# Ascend_SolePCB.net
KiCad netlist of a schematic drawn in EasyEDA Pro
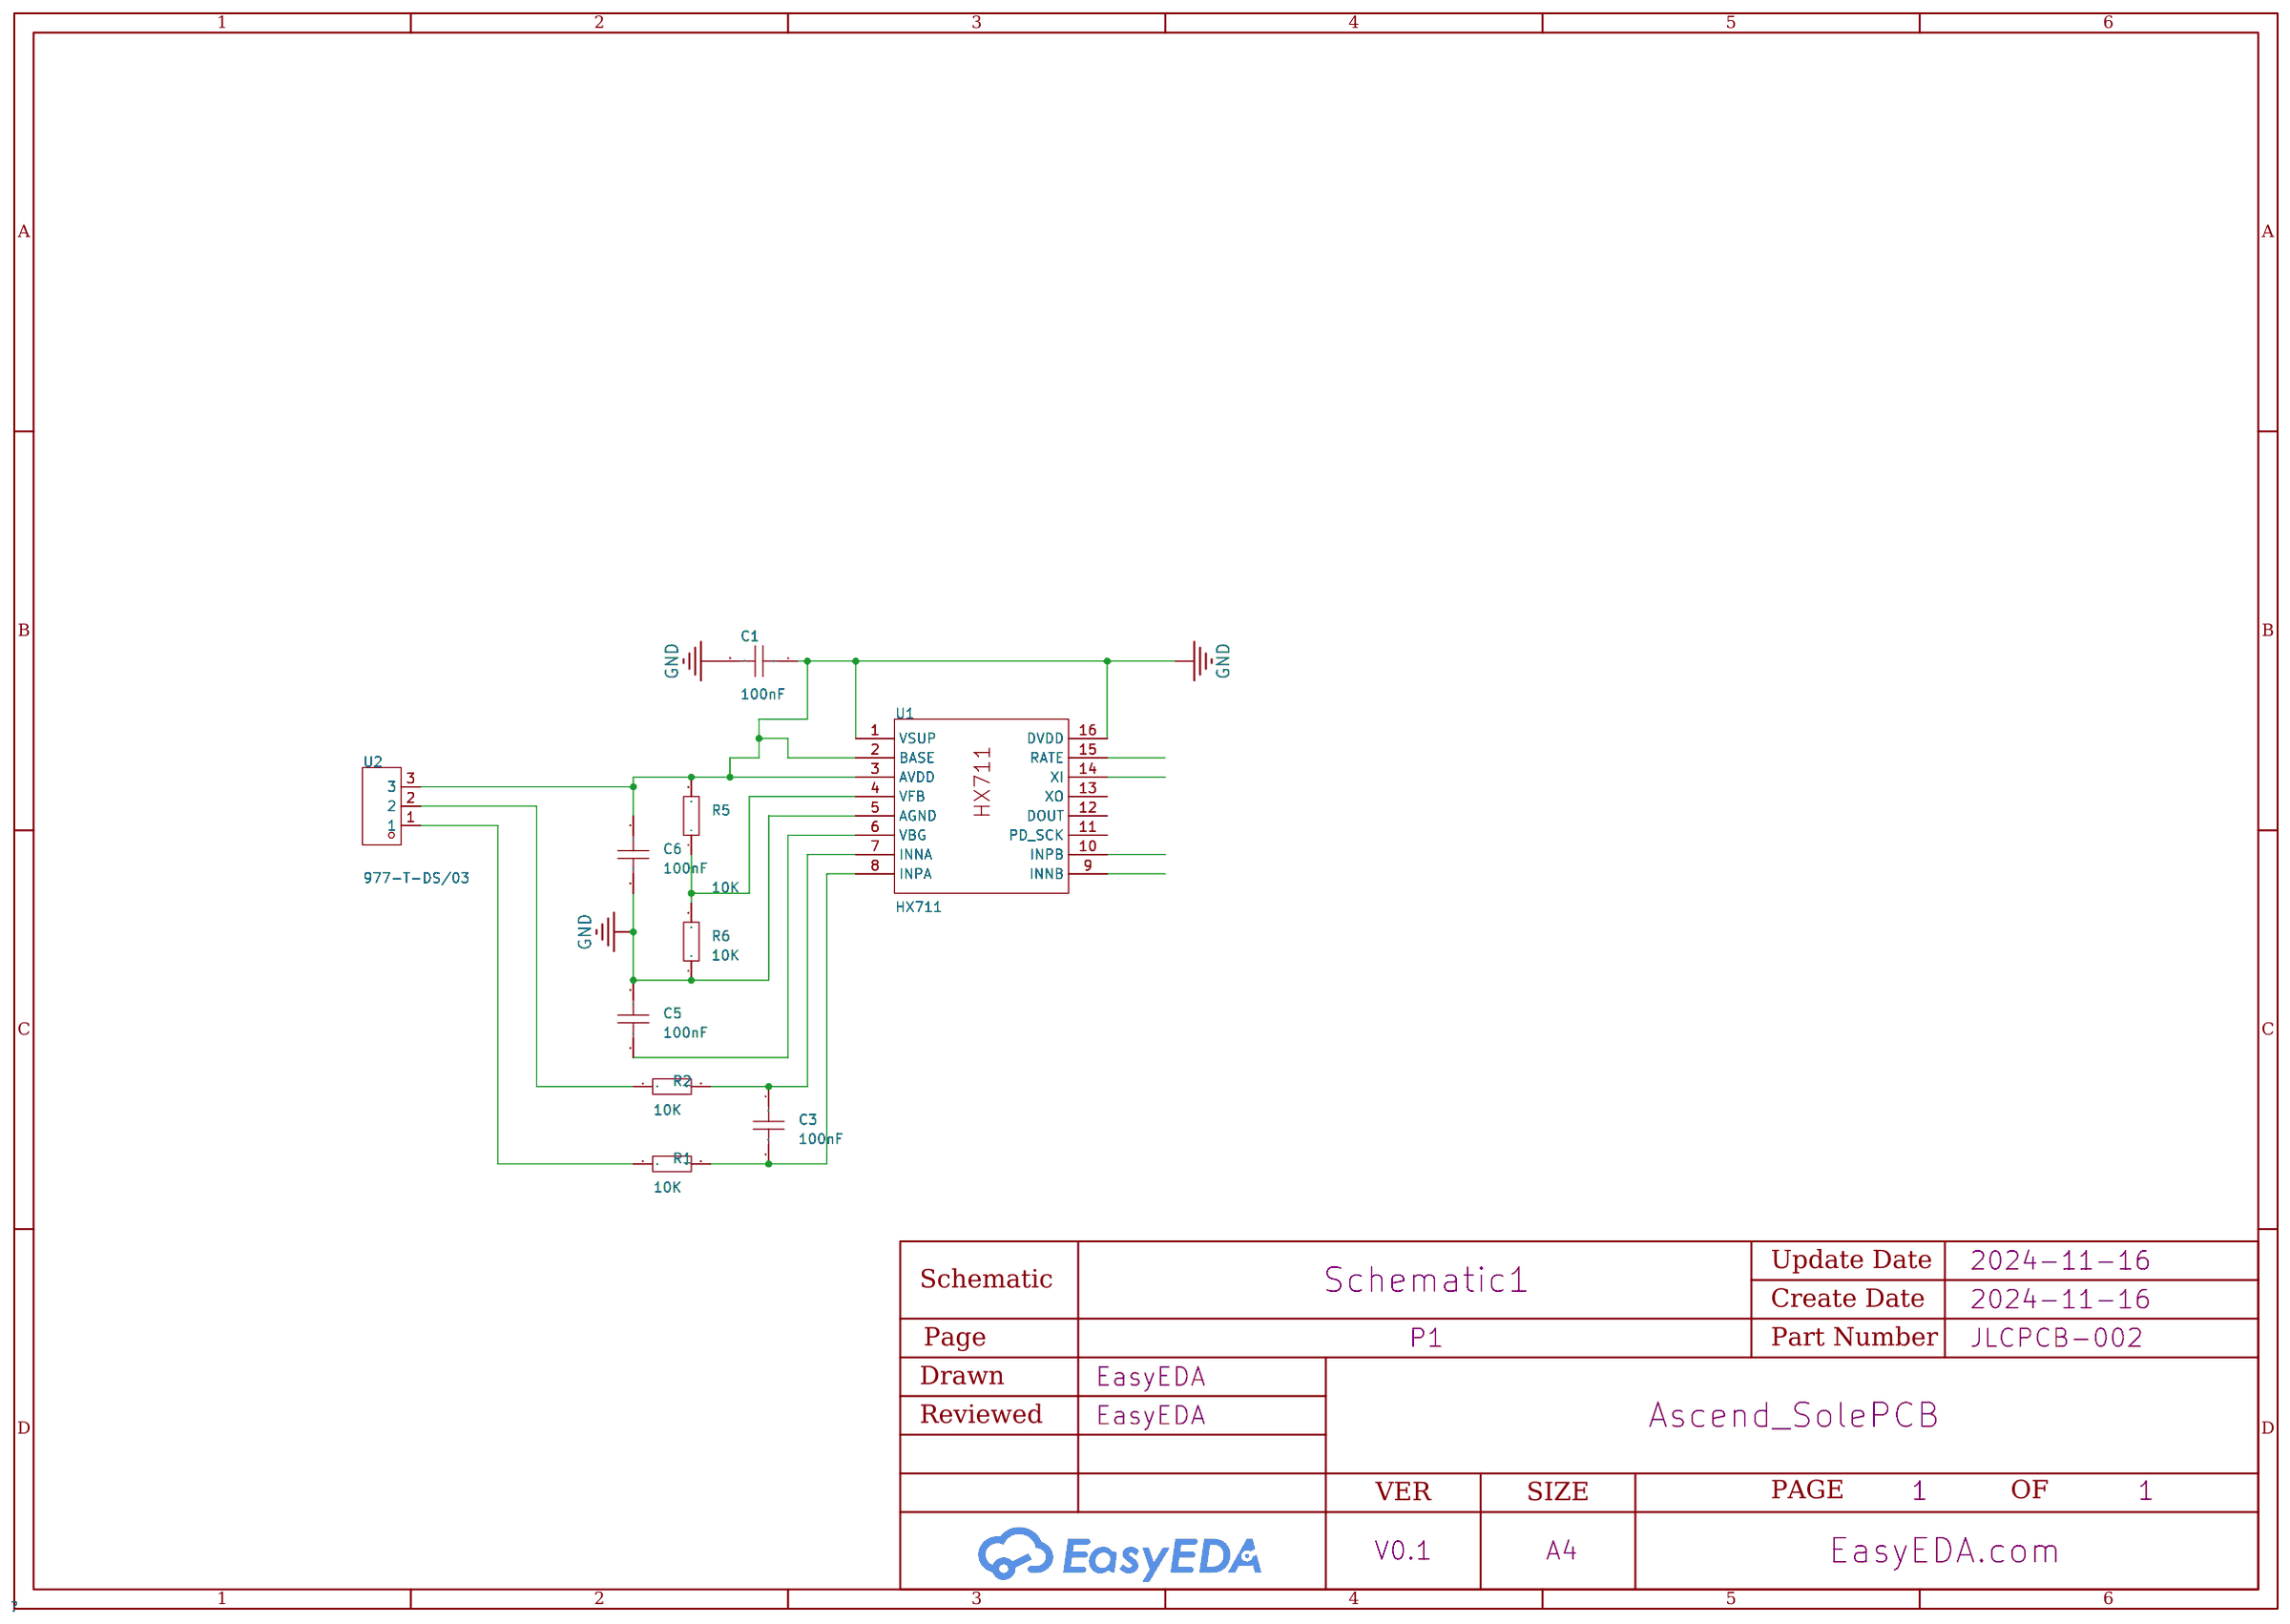
[diagram p0: schematic sheet]

(export (version "E")
  (design (tool "Eeschema 10.0.6"))
  (components
    (comp (ref "C1")
      (value "100nF")
      (footprint "easyedapro:C0201")
      (libsource (lib "easyedapro") (part "CAP"))
    )
    (comp (ref "C3")
      (value "100nF")
      (footprint "easyedapro:C0201")
      (libsource (lib "easyedapro") (part "CAP"))
    )
    (comp (ref "C5")
      (value "100nF")
      (footprint "easyedapro:C0201")
      (libsource (lib "easyedapro") (part "CAP"))
    )
    (comp (ref "C6")
      (value "100nF")
      (footprint "easyedapro:C0201")
      (libsource (lib "easyedapro") (part "CAP"))
    )
    (comp (ref "R1") (value "10K") (footprint "easyedapro:R0603") (libsource (lib "easyedapro") (part "Res")))
    (comp (ref "R2") (value "10K") (footprint "easyedapro:R0603") (libsource (lib "easyedapro") (part "Res")))
    (comp (ref "R5") (value "10K") (footprint "easyedapro:R0603") (libsource (lib "easyedapro") (part "Res")))
    (comp (ref "R6") (value "10K") (footprint "easyedapro:R0603") (libsource (lib "easyedapro") (part "Res")))
    (comp (ref "U1")
      (value "HX711")
      (footprint "easyedapro:SOP-16_L10.0-W3.9-P1.27-LS6.0-BL")
      (fields (field (name "Manufacturer") "AVIA(海芯科技)"))
      (libsource (lib "easyedapro") (part "HX711"))
    )
    (comp (ref "U2")
      (value "977-T-DS/03")
      (footprint "easyedapro:CONN-TH_3P-P7.50_977-T-DS-03")
      (fields (field (name "Manufacturer") "WECO(威克德诺)"))
      (libsource (lib "easyedapro") (part "977-T-DS/03"))
    )
  )
  (nets
    (net (code "1") (name "GND") (class "Default")
      (node (ref "C1") (pin "1") (pinfunction "1_1") (pintype "input"))
      (node (ref "C1") (pin "2") (pinfunction "2_2") (pintype "input"))
      (node (ref "C5") (pin "1") (pinfunction "1_1") (pintype "input"))
      (node (ref "C6") (pin "1") (pinfunction "1_1") (pintype "input"))
      (node (ref "C6") (pin "2") (pinfunction "2_2") (pintype "input"))
      (node (ref "R5") (pin "2") (pinfunction "2_2") (pintype "input"))
      (node (ref "R6") (pin "1") (pinfunction "1_1") (pintype "input"))
      (node (ref "U1") (pin "1") (pinfunction "VSUP_1") (pintype "unspecified"))
      (node (ref "U1") (pin "16") (pinfunction "DVDD_16") (pintype "unspecified"))
      (node (ref "U1") (pin "2") (pinfunction "BASE_2") (pintype "unspecified"))
      (node (ref "U1") (pin "3") (pinfunction "AVDD_3") (pintype "unspecified"))
      (node (ref "U1") (pin "5") (pinfunction "AGND_5") (pintype "unspecified"))
      (node (ref "U2") (pin "3") (pinfunction "3_3") (pintype "unspecified"))
    )
    (net (code "2") (name "Net-(R1-Pad1)") (class "Default")
      (node (ref "R1") (pin "1") (pinfunction "1_1") (pintype "input"))
      (node (ref "U2") (pin "1") (pinfunction "1_1") (pintype "unspecified"))
    )
    (net (code "3") (name "Net-(R2-Pad1)") (class "Default")
      (node (ref "R2") (pin "1") (pinfunction "1_1") (pintype "input"))
      (node (ref "U2") (pin "2") (pinfunction "2_2") (pintype "unspecified"))
    )
    (net (code "4") (name "Net-(U1-INNA)") (class "Default")
      (node (ref "C3") (pin "1") (pinfunction "1_1") (pintype "input"))
      (node (ref "R2") (pin "2") (pinfunction "2_2") (pintype "input"))
      (node (ref "U1") (pin "7") (pinfunction "INNA_7") (pintype "unspecified"))
    )
    (net (code "5") (name "Net-(U1-INPA)") (class "Default")
      (node (ref "C3") (pin "2") (pinfunction "2_2") (pintype "input"))
      (node (ref "R1") (pin "2") (pinfunction "2_2") (pintype "input"))
      (node (ref "U1") (pin "8") (pinfunction "INPA_8") (pintype "unspecified"))
    )
    (net (code "6") (name "Net-(U1-VBG)") (class "Default")
      (node (ref "C5") (pin "2") (pinfunction "2_2") (pintype "input"))
      (node (ref "U1") (pin "6") (pinfunction "VBG_6") (pintype "unspecified"))
    )
    (net (code "7") (name "Net-(U1-VFB)") (class "Default")
      (node (ref "R5") (pin "1") (pinfunction "1_1") (pintype "input"))
      (node (ref "R6") (pin "2") (pinfunction "2_2") (pintype "input"))
      (node (ref "U1") (pin "4") (pinfunction "VFB_4") (pintype "unspecified"))
    )
    (net (code "8") (name "unconnected-(U1-DOUT-Pad12)") (class "Default")
      (node (ref "U1") (pin "12") (pinfunction "DOUT_12") (pintype "unspecified"))
    )
    (net (code "9") (name "unconnected-(U1-INNB-Pad9)") (class "Default")
      (node (ref "U1") (pin "9") (pinfunction "INNB_9") (pintype "unspecified"))
    )
    (net (code "10") (name "unconnected-(U1-INPB-Pad10)") (class "Default")
      (node (ref "U1") (pin "10") (pinfunction "INPB_10") (pintype "unspecified"))
    )
    (net (code "11") (name "unconnected-(U1-PD_SCK-Pad11)") (class "Default")
      (node (ref "U1") (pin "11") (pinfunction "PD_SCK_11") (pintype "unspecified"))
    )
    (net (code "12") (name "unconnected-(U1-RATE-Pad15)") (class "Default")
      (node (ref "U1") (pin "15") (pinfunction "RATE_15") (pintype "unspecified"))
    )
    (net (code "13") (name "unconnected-(U1-XI-Pad14)") (class "Default")
      (node (ref "U1") (pin "14") (pinfunction "XI_14") (pintype "unspecified"))
    )
    (net (code "14") (name "unconnected-(U1-XO-Pad13)") (class "Default")
      (node (ref "U1") (pin "13") (pinfunction "XO_13") (pintype "unspecified"))
    )
  )
)
